# rapidshark-half-assed-half-h-bridge-mk-3.net
KiCad netlist of a schematic drawn in EAGLE
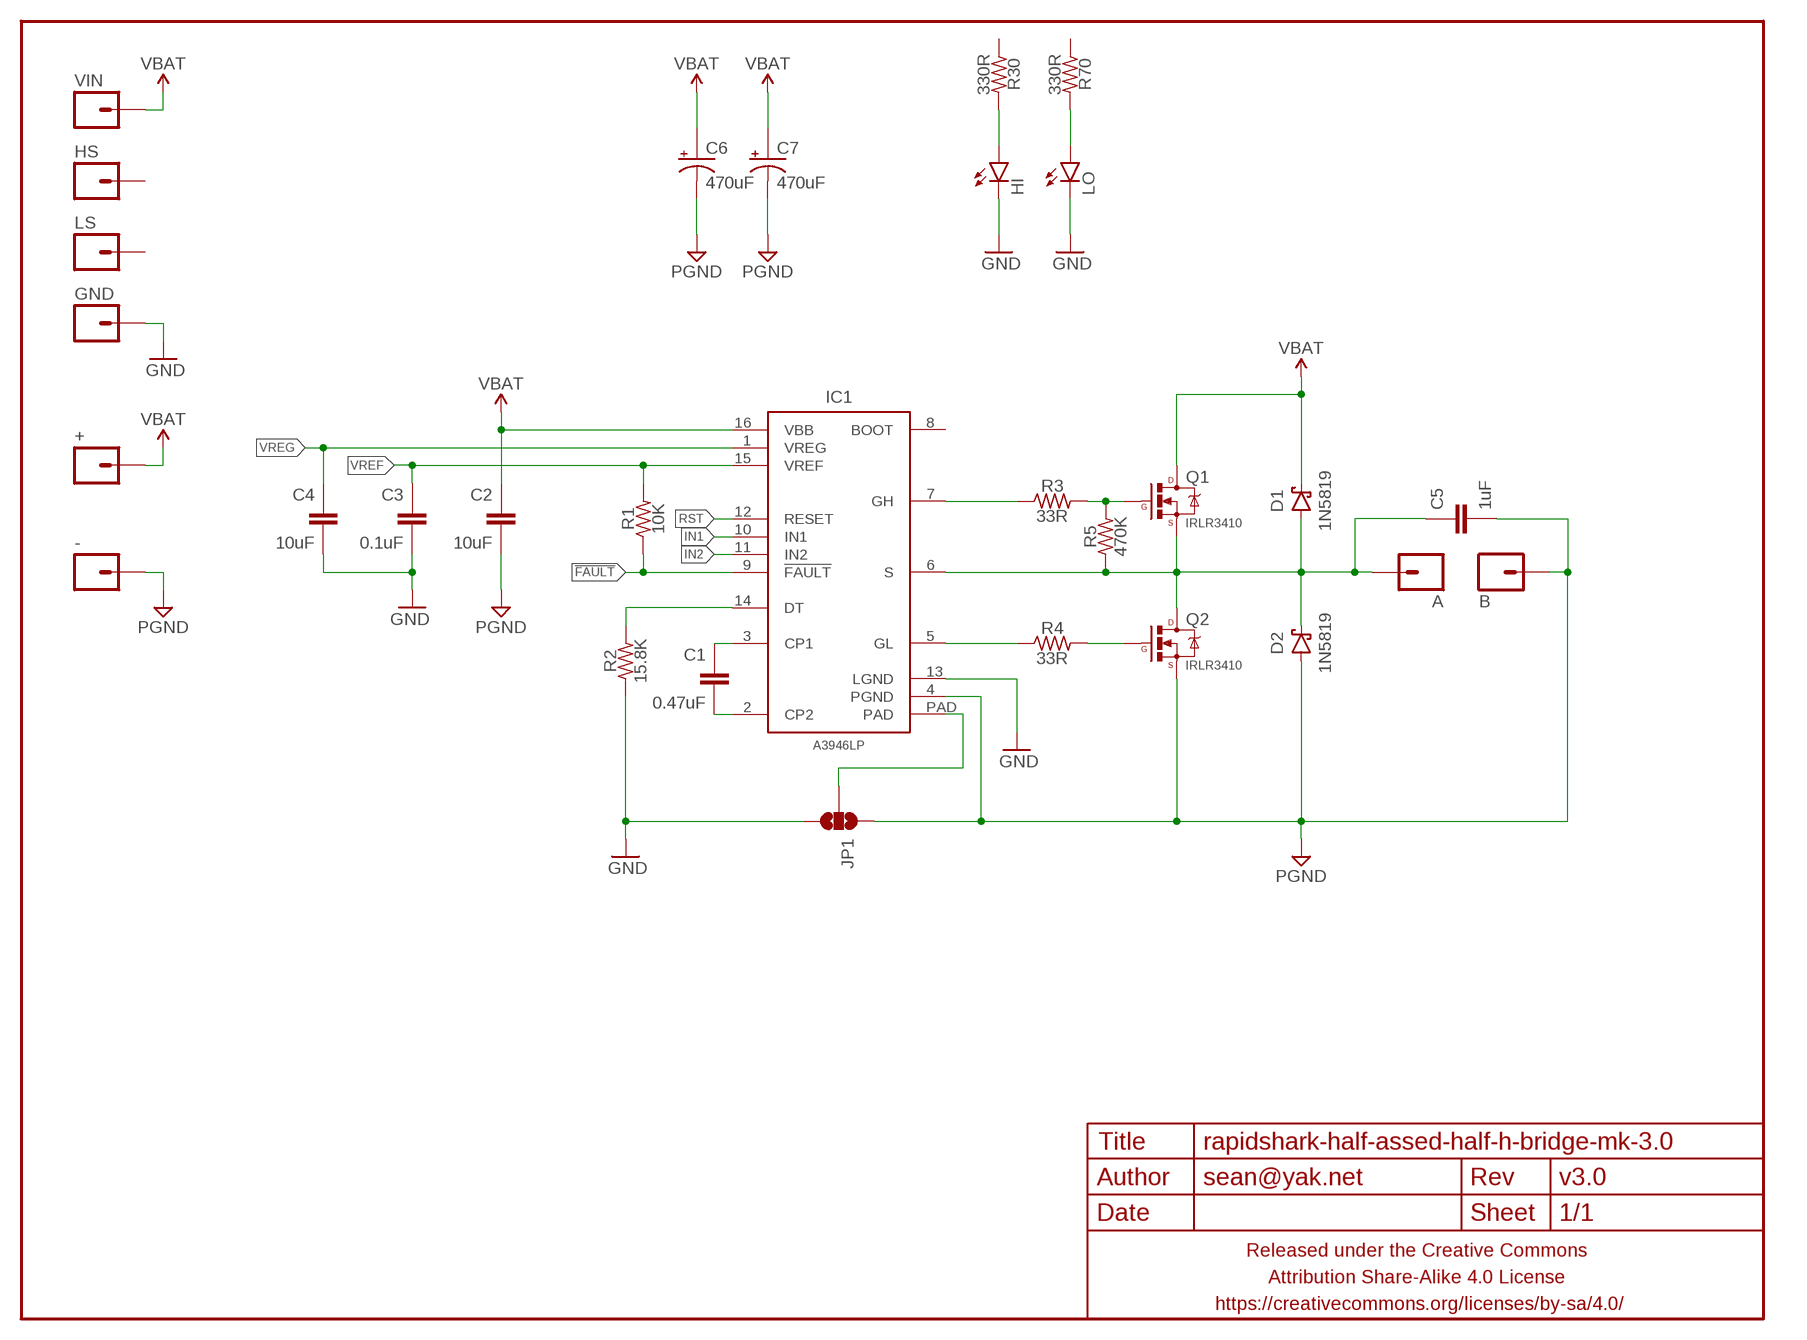
[diagram p0: schematic, sheet 1]

(export (version "E")
  (design (tool "Eeschema 10.0.6"))
  (components
    (comp (ref "+")
      (value "M01PTH-1.9MM")
      (footprint "eagle-import:1X01-1.9MM-CIR")
      (libsource (lib "eagle-import") (part "M01PTH-1.9MM"))
    )
    (comp (ref "-")
      (value "M01PTH-1.9MM")
      (footprint "eagle-import:1X01-1.9MM-CIR")
      (libsource (lib "eagle-import") (part "M01PTH-1.9MM"))
    )
    (comp (ref "A")
      (value "M01PTH-1.9MM")
      (footprint "eagle-import:1X01-1.9MM-CIR")
      (libsource (lib "eagle-import") (part "M01PTH-1.9MM"))
    )
    (comp (ref "B")
      (value "M01PTH-1.9MM")
      (footprint "eagle-import:1X01-1.9MM-CIR")
      (libsource (lib "eagle-import") (part "M01PTH-1.9MM"))
    )
    (comp (ref "C1")
      (value "0.47uF")
      (footprint "eagle-import:C0603-TIGHTER")
      (libsource (lib "eagle-import") (part "CAPACITOR-CERAMICC0603-TIGHTER"))
    )
    (comp (ref "C2")
      (value "10uF")
      (footprint "eagle-import:C0805-TIGHTER")
      (libsource (lib "eagle-import") (part "CAPACITOR-CERAMICC0805-TIGHTER"))
    )
    (comp (ref "C3")
      (value "0.1uF")
      (footprint "eagle-import:C0603-TIGHTER")
      (libsource (lib "eagle-import") (part "CAPACITOR-CERAMICC0603-TIGHTER"))
    )
    (comp (ref "C4")
      (value "10uF")
      (footprint "eagle-import:C0805-TIGHTER")
      (libsource (lib "eagle-import") (part "CAPACITOR-CERAMICC0805-TIGHTER"))
    )
    (comp (ref "C5")
      (value "1uF")
      (footprint "eagle-import:C0603-TIGHTER")
      (libsource (lib "eagle-import") (part "CAPACITOR-CERAMICC0603-TIGHTER"))
    )
    (comp (ref "C6")
      (value "470uF")
      (footprint "eagle-import:E5-10,5")
      (libsource (lib "eagle-import") (part "CAPACITOR-POLARIZEDE5-10.5"))
    )
    (comp (ref "C7")
      (value "470uF")
      (footprint "eagle-import:E5-10,5")
      (libsource (lib "eagle-import") (part "CAPACITOR-POLARIZEDE5-10.5"))
    )
    (comp (ref "D1")
      (value "1N5819")
      (footprint "eagle-import:SMA-DIODE-SCHOTTKY")
      (libsource (lib "eagle-import") (part "DIODE-SCHOTTKYSMA"))
    )
    (comp (ref "D2")
      (value "1N5819")
      (footprint "eagle-import:SMA-DIODE-SCHOTTKY")
      (libsource (lib "eagle-import") (part "DIODE-SCHOTTKYSMA"))
    )
    (comp (ref "FRAME1")
      (value "FRAME-LETTERNO_PACKAGE")
      (footprint "eagle-import:DUMMY")
      (fields (field (name "DESIGNER") "sean@yak.net") (field (name "VERSION") "v3.0"))
      (libsource (lib "eagle-import") (part "FRAME-LETTERNO_PACKAGE"))
    )
    (comp (ref "GND")
      (value "M01PTH")
      (footprint "eagle-import:1X01")
      (libsource (lib "eagle-import") (part "M01PTH"))
    )
    (comp (ref "HI")
      (value "LED0603-TIGHT")
      (footprint "eagle-import:LED-0603-TIGHT")
      (libsource (lib "eagle-import") (part "LED0603-TIGHT"))
    )
    (comp (ref "HS")
      (value "M01PTH")
      (footprint "eagle-import:1X01")
      (libsource (lib "eagle-import") (part "M01PTH"))
    )
    (comp (ref "IC1")
      (value "A3946LP")
      (footprint "eagle-import:TSSOP-16-PAD")
      (libsource (lib "eagle-import") (part "A3946LP"))
    )
    (comp (ref "JP1")
      (value "JUMPER-PAD-3-NOFULL_BOX_SILK")
      (footprint "eagle-import:PAD-JUMPER-3-NO_YES_SILK_FULL_BOX")
      (libsource (lib "eagle-import") (part "JUMPER-PAD-3-NOFULL_BOX_SILK"))
    )
    (comp (ref "LO")
      (value "LED0603-TIGHT")
      (footprint "eagle-import:LED-0603-TIGHT")
      (libsource (lib "eagle-import") (part "LED0603-TIGHT"))
    )
    (comp (ref "LS")
      (value "M01PTH")
      (footprint "eagle-import:1X01")
      (libsource (lib "eagle-import") (part "M01PTH"))
    )
    (comp (ref "Q1")
      (value "IRLR3410")
      (footprint "eagle-import:DPAK")
      (libsource (lib "eagle-import") (part "MOSFET-NCHANNELFDD8780"))
    )
    (comp (ref "Q2")
      (value "IRLR3410")
      (footprint "eagle-import:DPAK")
      (libsource (lib "eagle-import") (part "MOSFET-NCHANNELFDD8780"))
    )
    (comp (ref "R1")
      (value "10K")
      (footprint "eagle-import:R0603-TIGHTER")
      (libsource (lib "eagle-import") (part "RESISTORR0603-TIGHTER"))
    )
    (comp (ref "R2")
      (value "15.8K")
      (footprint "eagle-import:R0603-TIGHTER")
      (libsource (lib "eagle-import") (part "RESISTORR0603-TIGHTER"))
    )
    (comp (ref "R3")
      (value "33R")
      (footprint "eagle-import:R0603-TIGHTER")
      (libsource (lib "eagle-import") (part "RESISTORR0603-TIGHTER"))
    )
    (comp (ref "R4")
      (value "33R")
      (footprint "eagle-import:R0603-TIGHTER")
      (libsource (lib "eagle-import") (part "RESISTORR0603-TIGHTER"))
    )
    (comp (ref "R5")
      (value "470K")
      (footprint "eagle-import:R0603-TIGHTER")
      (libsource (lib "eagle-import") (part "RESISTORR0603-TIGHTER"))
    )
    (comp (ref "R30")
      (value "330R")
      (footprint "eagle-import:R0603-TIGHTER")
      (libsource (lib "eagle-import") (part "RESISTORR0603-TIGHTER"))
    )
    (comp (ref "R70")
      (value "330R")
      (footprint "eagle-import:R0603-TIGHTER")
      (libsource (lib "eagle-import") (part "RESISTORR0603-TIGHTER"))
    )
    (comp (ref "VIN")
      (value "M01PTH")
      (footprint "eagle-import:1X01")
      (libsource (lib "eagle-import") (part "M01PTH"))
    )
  )
  (nets
    (net (code "1") (name "/~{FAULT}") (class "Default")
      (node (ref "IC1") (pin "9") (pinfunction "~{FAULT}_9") (pintype "bidirectional"))
      (node (ref "R1") (pin "1") (pinfunction "1_1") (pintype "passive"))
    )
    (net (code "2") (name "GND") (class "Default")
      (node (ref "C3") (pin "2") (pinfunction "2_2") (pintype "passive"))
      (node (ref "C4") (pin "2") (pinfunction "2_2") (pintype "passive"))
      (node (ref "GND") (pin "1") (pinfunction "1_1") (pintype "passive"))
      (node (ref "HI") (pin "C") (pinfunction "C_C") (pintype "passive"))
      (node (ref "IC1") (pin "13") (pinfunction "LGND_13") (pintype "bidirectional"))
      (node (ref "JP1") (pin "3") (pinfunction "3_3") (pintype "passive"))
      (node (ref "LO") (pin "C") (pinfunction "C_C") (pintype "passive"))
      (node (ref "R2") (pin "1") (pinfunction "1_1") (pintype "passive"))
    )
    (net (code "3") (name "IN1") (class "Default")
      (node (ref "IC1") (pin "10") (pinfunction "IN1_10") (pintype "bidirectional"))
    )
    (net (code "4") (name "IN2") (class "Default")
      (node (ref "IC1") (pin "11") (pinfunction "IN2_11") (pintype "bidirectional"))
    )
    (net (code "5") (name "Net-(A-1)") (class "Default")
      (node (ref "A") (pin "P$1") (pinfunction "1_P$1") (pintype "passive"))
      (node (ref "C5") (pin "1") (pinfunction "1_1") (pintype "passive"))
      (node (ref "D1") (pin "A") (pinfunction "A_A") (pintype "passive"))
      (node (ref "D2") (pin "C") (pinfunction "C_C") (pintype "passive"))
      (node (ref "IC1") (pin "6") (pinfunction "S_6") (pintype "bidirectional"))
      (node (ref "Q1") (pin "3") (pinfunction "S_3") (pintype "passive"))
      (node (ref "Q2") (pin "4") (pinfunction "D_4") (pintype "passive"))
      (node (ref "R5") (pin "1") (pinfunction "1_1") (pintype "passive"))
    )
    (net (code "6") (name "Net-(HI-PadA)") (class "Default")
      (node (ref "HI") (pin "A") (pinfunction "A_A") (pintype "passive"))
      (node (ref "R30") (pin "2") (pinfunction "2_2") (pintype "passive"))
    )
    (net (code "7") (name "Net-(IC1-CP1)") (class "Default")
      (node (ref "C1") (pin "1") (pinfunction "1_1") (pintype "passive"))
      (node (ref "IC1") (pin "3") (pinfunction "CP1_3") (pintype "bidirectional"))
    )
    (net (code "8") (name "Net-(IC1-CP2)") (class "Default")
      (node (ref "C1") (pin "2") (pinfunction "2_2") (pintype "passive"))
      (node (ref "IC1") (pin "2") (pinfunction "CP2_2") (pintype "bidirectional"))
    )
    (net (code "9") (name "Net-(IC1-DT)") (class "Default")
      (node (ref "IC1") (pin "14") (pinfunction "DT_14") (pintype "bidirectional"))
      (node (ref "R2") (pin "2") (pinfunction "2_2") (pintype "passive"))
    )
    (net (code "10") (name "Net-(IC1-GH)") (class "Default")
      (node (ref "IC1") (pin "7") (pinfunction "GH_7") (pintype "bidirectional"))
      (node (ref "R3") (pin "1") (pinfunction "1_1") (pintype "passive"))
    )
    (net (code "11") (name "Net-(IC1-GL)") (class "Default")
      (node (ref "IC1") (pin "5") (pinfunction "GL_5") (pintype "bidirectional"))
      (node (ref "R4") (pin "1") (pinfunction "1_1") (pintype "passive"))
    )
    (net (code "12") (name "Net-(IC1-PadPAD)") (class "Default")
      (node (ref "IC1") (pin "PAD") (pinfunction "PAD_PAD") (pintype "bidirectional"))
      (node (ref "JP1") (pin "2") (pinfunction "2_2") (pintype "passive"))
    )
    (net (code "13") (name "Net-(LO-PadA)") (class "Default")
      (node (ref "LO") (pin "A") (pinfunction "A_A") (pintype "passive"))
      (node (ref "R70") (pin "2") (pinfunction "2_2") (pintype "passive"))
    )
    (net (code "14") (name "Net-(Q1-G)") (class "Default")
      (node (ref "Q1") (pin "1") (pinfunction "G_1") (pintype "passive"))
      (node (ref "R3") (pin "2") (pinfunction "2_2") (pintype "passive"))
      (node (ref "R5") (pin "2") (pinfunction "2_2") (pintype "passive"))
    )
    (net (code "15") (name "Net-(Q2-G)") (class "Default")
      (node (ref "Q2") (pin "1") (pinfunction "G_1") (pintype "passive"))
      (node (ref "R4") (pin "2") (pinfunction "2_2") (pintype "passive"))
    )
    (net (code "16") (name "PGND") (class "Default")
      (node (ref "-") (pin "P$1") (pinfunction "1_P$1") (pintype "passive"))
      (node (ref "B") (pin "P$1") (pinfunction "1_P$1") (pintype "passive"))
      (node (ref "C2") (pin "2") (pinfunction "2_2") (pintype "passive"))
      (node (ref "C5") (pin "2") (pinfunction "2_2") (pintype "passive"))
      (node (ref "C6") (pin "-") (pinfunction "-_-") (pintype "passive"))
      (node (ref "C7") (pin "-") (pinfunction "-_-") (pintype "passive"))
      (node (ref "D2") (pin "A") (pinfunction "A_A") (pintype "passive"))
      (node (ref "IC1") (pin "4") (pinfunction "PGND_4") (pintype "bidirectional"))
      (node (ref "JP1") (pin "1") (pinfunction "1_1") (pintype "passive"))
      (node (ref "Q2") (pin "3") (pinfunction "S_3") (pintype "passive"))
    )
    (net (code "17") (name "RST") (class "Default")
      (node (ref "IC1") (pin "12") (pinfunction "RESET_12") (pintype "bidirectional"))
    )
    (net (code "18") (name "VBAT") (class "Default")
      (node (ref "+") (pin "P$1") (pinfunction "1_P$1") (pintype "passive"))
      (node (ref "C2") (pin "1") (pinfunction "1_1") (pintype "passive"))
      (node (ref "C6") (pin "+") (pinfunction "+_+") (pintype "passive"))
      (node (ref "C7") (pin "+") (pinfunction "+_+") (pintype "passive"))
      (node (ref "D1") (pin "C") (pinfunction "C_C") (pintype "passive"))
      (node (ref "IC1") (pin "16") (pinfunction "VBB_16") (pintype "bidirectional"))
      (node (ref "Q1") (pin "4") (pinfunction "D_4") (pintype "passive"))
      (node (ref "VIN") (pin "1") (pinfunction "1_1") (pintype "passive"))
    )
    (net (code "19") (name "VREF") (class "Default")
      (node (ref "C3") (pin "1") (pinfunction "1_1") (pintype "passive"))
      (node (ref "IC1") (pin "15") (pinfunction "VREF_15") (pintype "bidirectional"))
      (node (ref "R1") (pin "2") (pinfunction "2_2") (pintype "passive"))
    )
    (net (code "20") (name "VREG") (class "Default")
      (node (ref "C4") (pin "1") (pinfunction "1_1") (pintype "passive"))
      (node (ref "IC1") (pin "1") (pinfunction "VREG_1") (pintype "bidirectional"))
    )
    (net (code "21") (name "unconnected-(HS-Pad1)") (class "Default")
      (node (ref "HS") (pin "1") (pinfunction "1_1") (pintype "passive"))
    )
    (net (code "22") (name "unconnected-(IC1-BOOT-Pad8)") (class "Default")
      (node (ref "IC1") (pin "8") (pinfunction "BOOT_8") (pintype "bidirectional"))
    )
    (net (code "23") (name "unconnected-(LS-Pad1)") (class "Default")
      (node (ref "LS") (pin "1") (pinfunction "1_1") (pintype "passive"))
    )
    (net (code "24") (name "unconnected-(R30-Pad1)") (class "Default")
      (node (ref "R30") (pin "1") (pinfunction "1_1") (pintype "passive"))
    )
    (net (code "25") (name "unconnected-(R70-Pad1)") (class "Default")
      (node (ref "R70") (pin "1") (pinfunction "1_1") (pintype "passive"))
    )
  )
)
